# 0241_Current_Measurement.net
KiCad netlist of a schematic drawn in EAGLE
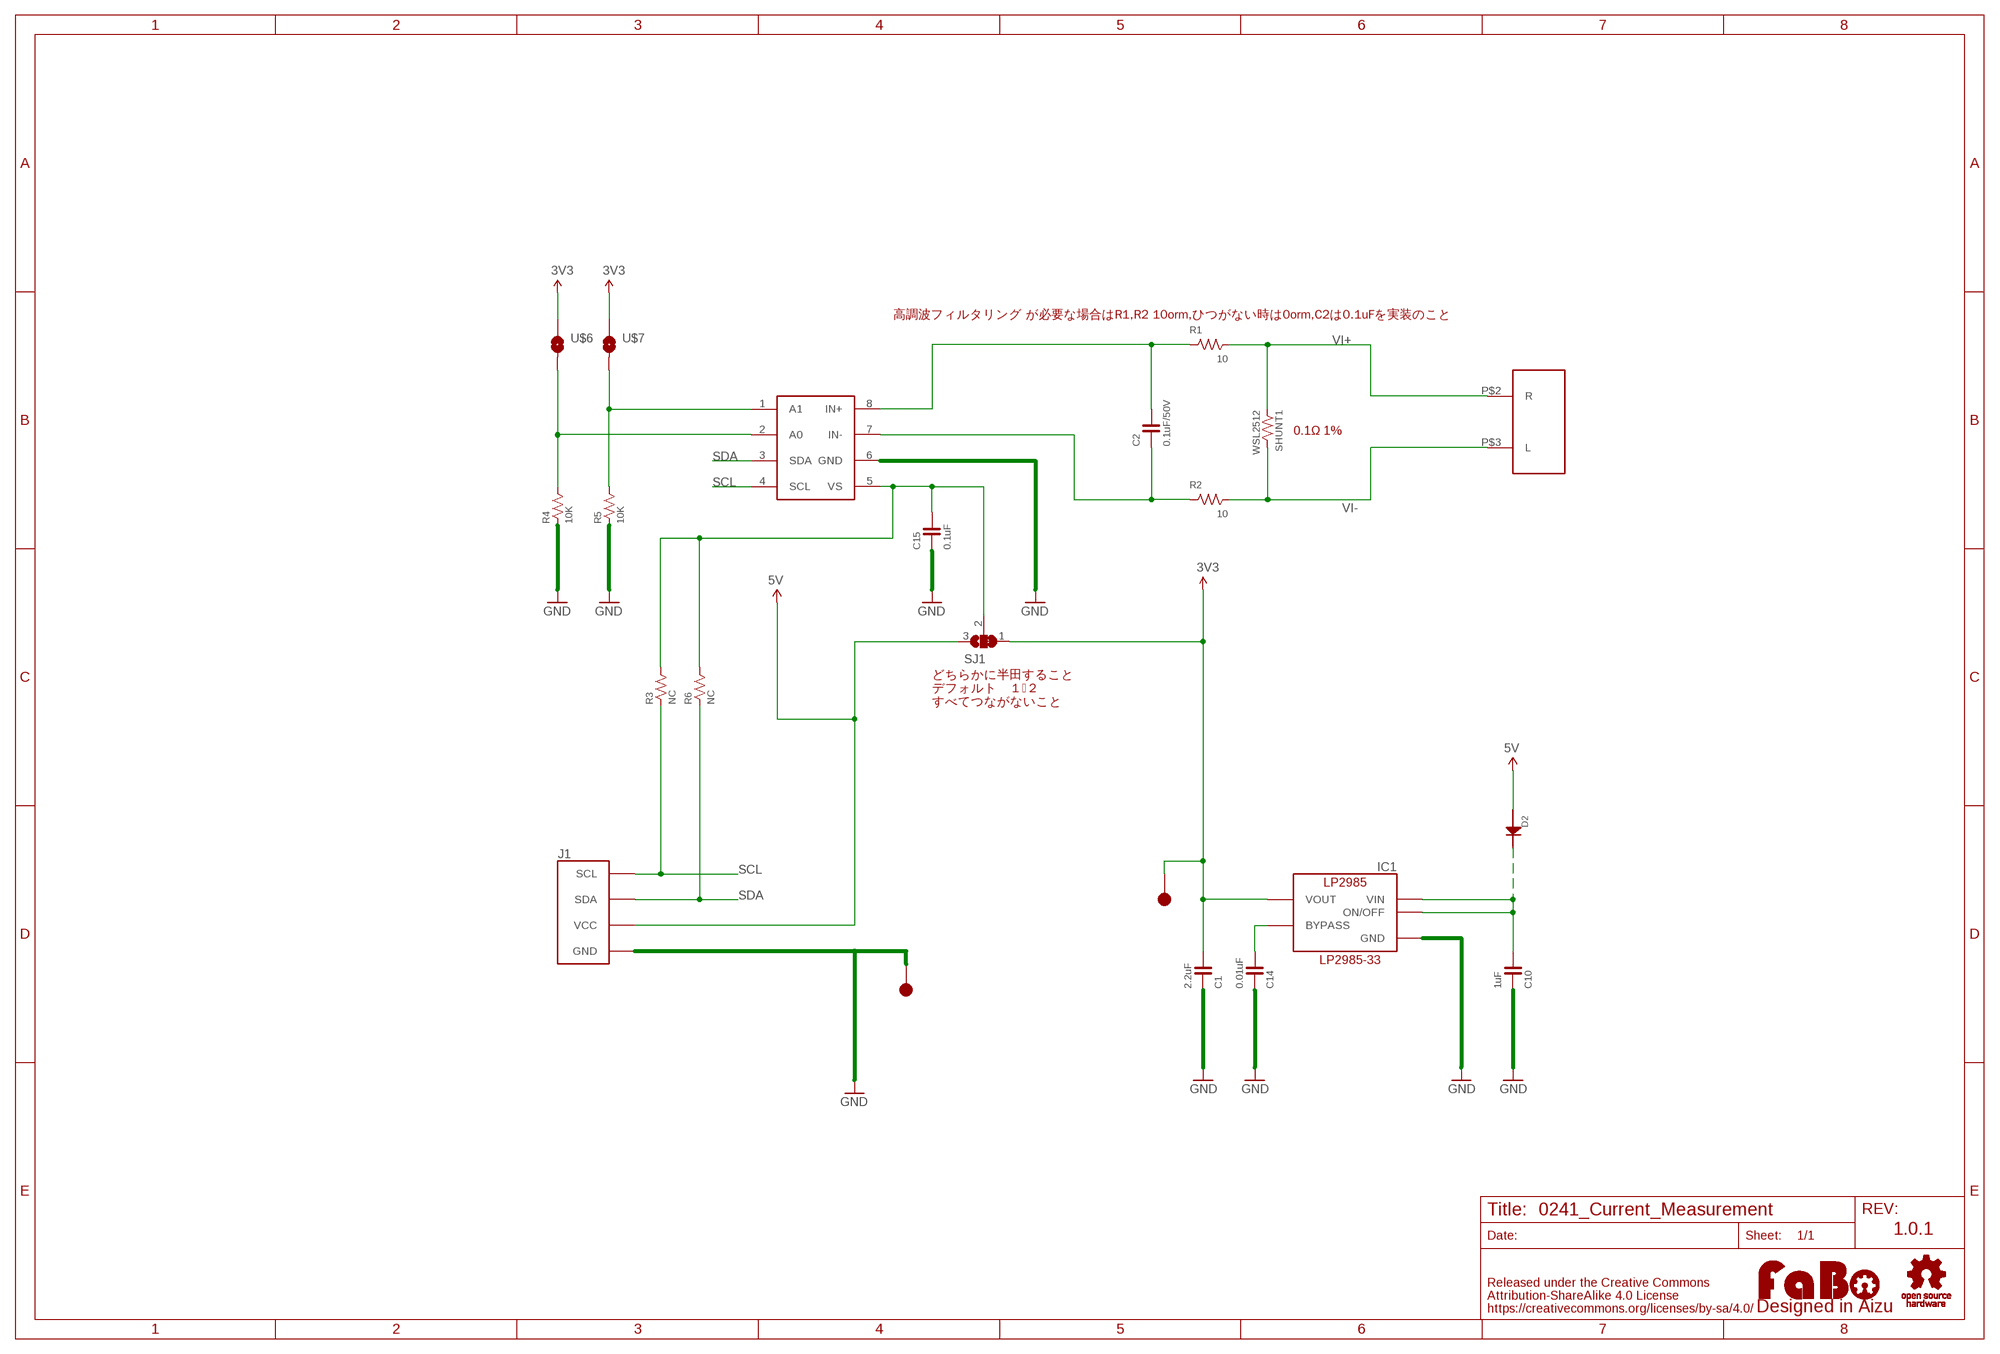
[diagram p0: schematic, sheet 1]

(export (version "E")
  (design (tool "Eeschema 10.0.6"))
  (components
    (comp (ref "C1")
      (value "2.2uF")
      (footprint "eagle-import:0603")
      (libsource (lib "eagle-import") (part "CAPACITOR-0603"))
    )
    (comp (ref "C2")
      (value "0.1uF/50V")
      (footprint "eagle-import:0603")
      (libsource (lib "eagle-import") (part "CAPACITOR-0603"))
    )
    (comp (ref "C10")
      (value "1uF")
      (footprint "eagle-import:0603")
      (libsource (lib "eagle-import") (part "CAPACITOR-0603"))
    )
    (comp (ref "C14")
      (value "0.01uF")
      (footprint "eagle-import:0603")
      (libsource (lib "eagle-import") (part "CAPACITOR-0603"))
    )
    (comp (ref "C15")
      (value "0.1uF")
      (footprint "eagle-import:0603")
      (libsource (lib "eagle-import") (part "CAPACITOR-0603"))
    )
    (comp (ref "D2")
      (value "1N4148")
      (footprint "eagle-import:1N4148W")
      (libsource (lib "eagle-import") (part "1N4148"))
    )
    (comp (ref "IC1")
      (value "LP2985-33")
      (footprint "eagle-import:SOT-23-5")
      (libsource (lib "eagle-import") (part "LP2985-33DBV"))
    )
    (comp (ref "J1")
      (value "FABO_BRICK_I2C-S04B-PASK-2")
      (footprint "eagle-import:FABO_BRICK_I2C_S04B-PASK-2")
      (libsource (lib "eagle-import") (part "FABO_BRICK_I2C-S04B-PASK-2"))
    )
    (comp (ref "LOGO1")
      (value "LOGO_FABO-M")
      (footprint "eagle-import:LOGO_FABO_M")
      (libsource (lib "eagle-import") (part "LOGO_FABO-M"))
    )
    (comp (ref "R1")
      (value "10")
      (footprint "eagle-import:0603")
      (libsource (lib "eagle-import") (part "RESISTOR-0603"))
    )
    (comp (ref "R2")
      (value "10")
      (footprint "eagle-import:0603")
      (libsource (lib "eagle-import") (part "RESISTOR-0603"))
    )
    (comp (ref "R3")
      (value "NC")
      (footprint "eagle-import:0603")
      (libsource (lib "eagle-import") (part "RESISTOR-0603"))
    )
    (comp (ref "R4")
      (value "10K")
      (footprint "eagle-import:0603")
      (libsource (lib "eagle-import") (part "RESISTOR-0603"))
    )
    (comp (ref "R5")
      (value "10K")
      (footprint "eagle-import:0603")
      (libsource (lib "eagle-import") (part "RESISTOR-0603"))
    )
    (comp (ref "R6")
      (value "NC")
      (footprint "eagle-import:0603")
      (libsource (lib "eagle-import") (part "RESISTOR-0603"))
    )
    (comp (ref "SHUNT1")
      (value "WSL2512")
      (footprint "eagle-import:2512INCH")
      (libsource (lib "eagle-import") (part "WSL2512"))
    )
    (comp (ref "SJ1")
      (value "SJ2W")
      (footprint "eagle-import:SJ_2")
      (libsource (lib "eagle-import") (part "SJ2W"))
    )
    (comp (ref "TP1")
      (value "TP-15")
      (footprint "eagle-import:TP-15")
      (libsource (lib "eagle-import") (part "TP-15"))
    )
    (comp (ref "TP5")
      (value "TP-15")
      (footprint "eagle-import:TP-15")
      (libsource (lib "eagle-import") (part "TP-15"))
    )
    (comp (ref "U$1")
      (value "TI-INA219")
      (footprint "eagle-import:TI-INA219")
      (libsource (lib "eagle-import") (part "TI-INA219"))
    )
    (comp (ref "U$5")
      (value "2606-1102/020-000")
      (footprint "eagle-import:2606-1102_020-000")
      (libsource (lib "eagle-import") (part "2606-1102/020-000"))
    )
    (comp (ref "U$6")
      (value "FABO-SMD-JUMPER-SELECT-NARROW")
      (footprint "eagle-import:SMD-JUMPER_SELECT_NARROW")
      (libsource (lib "eagle-import") (part "FABO-SMD-JUMPER-SELECT-NARROW"))
    )
    (comp (ref "U$7")
      (value "FABO-SMD-JUMPER-SELECT-NARROW")
      (footprint "eagle-import:SMD-JUMPER_SELECT_NARROW")
      (libsource (lib "eagle-import") (part "FABO-SMD-JUMPER-SELECT-NARROW"))
    )
    (comp (ref "U$8")
      (value "LOGO_OSHW-M_BOTTOM")
      (footprint "eagle-import:LOGO_OSHW_M_BOTTOM")
      (libsource (lib "eagle-import") (part "LOGO_OSHW-M_BOTTOM"))
    )
  )
  (nets
    (net (code "1") (name "/SCL") (class "Default")
      (node (ref "J1") (pin "SCL") (pinfunction "SCL_SCL") (pintype "bidirectional"))
      (node (ref "R3") (pin "1") (pinfunction "1_1") (pintype "bidirectional"))
      (node (ref "U$1") (pin "4") (pinfunction "SCL_4") (pintype "bidirectional"))
    )
    (net (code "2") (name "/SDA") (class "Default")
      (node (ref "J1") (pin "SDA") (pinfunction "SDA_SDA") (pintype "bidirectional"))
      (node (ref "R6") (pin "1") (pinfunction "1_1") (pintype "bidirectional"))
      (node (ref "U$1") (pin "3") (pinfunction "SDA_3") (pintype "bidirectional"))
    )
    (net (code "3") (name "/VI+") (class "Default")
      (node (ref "R1") (pin "1") (pinfunction "1_1") (pintype "bidirectional"))
      (node (ref "SHUNT1") (pin "P$1") (pinfunction "1_P$1") (pintype "bidirectional"))
      (node (ref "U$5") (pin "P$2") (pinfunction "R_P$2") (pintype "bidirectional"))
    )
    (net (code "4") (name "/VI-") (class "Default")
      (node (ref "R2") (pin "1") (pinfunction "1_1") (pintype "bidirectional"))
      (node (ref "SHUNT1") (pin "P$2") (pinfunction "2_P$2") (pintype "bidirectional"))
      (node (ref "U$5") (pin "P$3") (pinfunction "L_P$3") (pintype "bidirectional"))
    )
    (net (code "5") (name "3V3") (class "Default")
      (node (ref "C1") (pin "2") (pinfunction "2_2") (pintype "passive"))
      (node (ref "IC1") (pin "5") (pinfunction "VOUT_5") (pintype "output"))
      (node (ref "SJ1") (pin "1") (pinfunction "1_1") (pintype "passive"))
      (node (ref "TP5") (pin "1") (pinfunction "1_1") (pintype "bidirectional"))
      (node (ref "U$6") (pin "1") (pinfunction "1_1") (pintype "passive"))
      (node (ref "U$7") (pin "1") (pinfunction "1_1") (pintype "passive"))
    )
    (net (code "6") (name "5V") (class "Default")
      (node (ref "D2") (pin "ANODE") (pinfunction "ANODE_ANODE") (pintype "bidirectional"))
      (node (ref "J1") (pin "VCC") (pinfunction "VCC_VCC") (pintype "bidirectional"))
      (node (ref "SJ1") (pin "3") (pinfunction "3_3") (pintype "passive"))
    )
    (net (code "7") (name "GND") (class "Default")
      (node (ref "C1") (pin "1") (pinfunction "1_1") (pintype "passive"))
      (node (ref "C10") (pin "1") (pinfunction "1_1") (pintype "passive"))
      (node (ref "C14") (pin "1") (pinfunction "1_1") (pintype "passive"))
      (node (ref "C15") (pin "1") (pinfunction "1_1") (pintype "passive"))
      (node (ref "IC1") (pin "2") (pinfunction "GND_2") (pintype "power_in"))
      (node (ref "J1") (pin "GND") (pinfunction "GND_GND") (pintype "bidirectional"))
      (node (ref "R4") (pin "1") (pinfunction "1_1") (pintype "bidirectional"))
      (node (ref "R5") (pin "1") (pinfunction "1_1") (pintype "bidirectional"))
      (node (ref "TP1") (pin "1") (pinfunction "1_1") (pintype "bidirectional"))
      (node (ref "U$1") (pin "6") (pinfunction "GND_6") (pintype "bidirectional"))
    )
    (net (code "8") (name "Net-(IC1-BYPASS)") (class "Default")
      (node (ref "C14") (pin "2") (pinfunction "2_2") (pintype "passive"))
      (node (ref "IC1") (pin "4") (pinfunction "BYPASS_4") (pintype "bidirectional"))
    )
    (net (code "9") (name "Net-(IC1-ON{slash}OFF)") (class "Default")
      (node (ref "C10") (pin "2") (pinfunction "2_2") (pintype "passive"))
      (node (ref "D2") (pin "CATHODE") (pinfunction "CATHODE_CATHODE") (pintype "bidirectional"))
      (node (ref "IC1") (pin "1") (pinfunction "VIN_1") (pintype "input"))
      (node (ref "IC1") (pin "3") (pinfunction "ON/OFF_3") (pintype "input"))
    )
    (net (code "10") (name "Net-(U$1-A0)") (class "Default")
      (node (ref "R4") (pin "2") (pinfunction "2_2") (pintype "bidirectional"))
      (node (ref "U$1") (pin "2") (pinfunction "A0_2") (pintype "bidirectional"))
      (node (ref "U$6") (pin "2") (pinfunction "2_2") (pintype "passive"))
    )
    (net (code "11") (name "Net-(U$1-A1)") (class "Default")
      (node (ref "R5") (pin "2") (pinfunction "2_2") (pintype "bidirectional"))
      (node (ref "U$1") (pin "1") (pinfunction "A1_1") (pintype "bidirectional"))
      (node (ref "U$7") (pin "2") (pinfunction "2_2") (pintype "passive"))
    )
    (net (code "12") (name "Net-(U$1-IN+)") (class "Default")
      (node (ref "C2") (pin "2") (pinfunction "2_2") (pintype "passive"))
      (node (ref "R1") (pin "2") (pinfunction "2_2") (pintype "bidirectional"))
      (node (ref "U$1") (pin "8") (pinfunction "IN+_8") (pintype "bidirectional"))
    )
    (net (code "13") (name "Net-(U$1-IN-)") (class "Default")
      (node (ref "C2") (pin "1") (pinfunction "1_1") (pintype "passive"))
      (node (ref "R2") (pin "2") (pinfunction "2_2") (pintype "bidirectional"))
      (node (ref "U$1") (pin "7") (pinfunction "IN-_7") (pintype "bidirectional"))
    )
    (net (code "14") (name "Net-(U$1-VS)") (class "Default")
      (node (ref "C15") (pin "2") (pinfunction "2_2") (pintype "passive"))
      (node (ref "R3") (pin "2") (pinfunction "2_2") (pintype "bidirectional"))
      (node (ref "R6") (pin "2") (pinfunction "2_2") (pintype "bidirectional"))
      (node (ref "SJ1") (pin "2") (pinfunction "2_2") (pintype "passive"))
      (node (ref "U$1") (pin "5") (pinfunction "VS_5") (pintype "bidirectional"))
    )
  )
)
